# Sheet2.net
KiCad netlist of a schematic drawn in Altium Designer
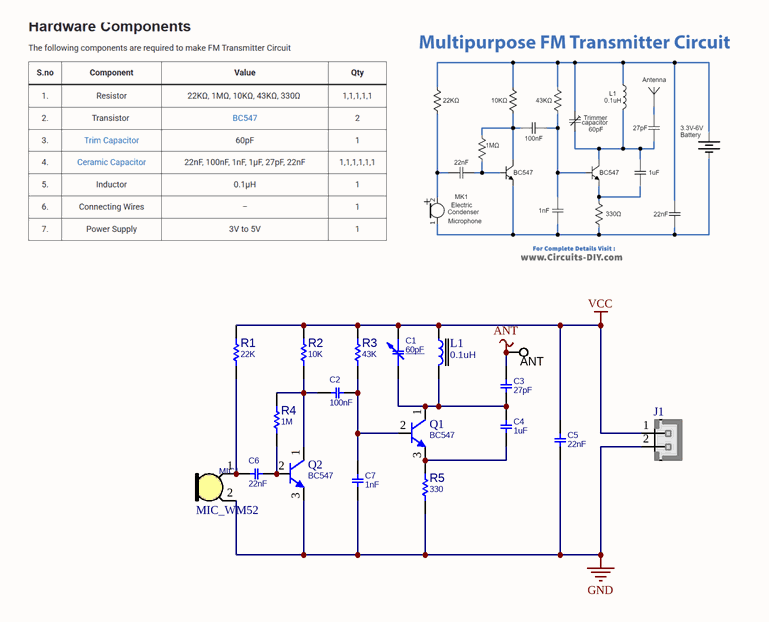
[diagram p0: Sheet2.SchDoc]

(export (version "E")
  (design (tool "Eeschema 10.0.6"))
  (components
    (comp (ref "ANT")
      (value "TESTPOINT_PROBE")
      (footprint "TPTHD_A")
      (description "TEST POINT")
      (fields (field (name "MANF") "MANF") (field (name "MANF_P#") "MANF_P#"))
      (libsource (lib "test-tp_jumper") (part "TESTPOINT_PROBE"))
    )
    (comp (ref "C1")
      (value "60pF")
      (footprint "CTRM_6X6")
      (description "CAP, THD, TRIMMER")
      (fields (field (name "MANF_P#") "MANF_PART#") (field (name "MANF") "MANF"))
      (libsource (lib "passive_thd") (part "CAP_THD_TRIMMER"))
    )
    (comp (ref "C2")
      (value "100nF")
      (footprint "C_CER_D5")
      (description "CAP, THD, CER MULTI LAYER,")
      (fields (field (name "MANF_P#") "MANF_PART#") (field (name "MANF") "MANF"))
      (libsource (lib "passive_thd") (part "CAP_THD_CER"))
    )
    (comp (ref "C3")
      (value "27pF")
      (footprint "C_CER_D5")
      (description "CAP, THD, CER MULTI LAYER,")
      (fields (field (name "MANF_P#") "MANF_PART#") (field (name "MANF") "MANF"))
      (libsource (lib "passive_thd") (part "CAP_THD_CER"))
    )
    (comp (ref "C4")
      (value "1uF")
      (footprint "C_CER_D5")
      (description "CAP, THD, CER MULTI LAYER,")
      (fields (field (name "MANF_P#") "MANF_PART#") (field (name "MANF") "MANF"))
      (libsource (lib "passive_thd") (part "CAP_THD_CER"))
    )
    (comp (ref "C5")
      (value "22nF")
      (footprint "C_CER_D5")
      (description "CAP, THD, CER MULTI LAYER,")
      (fields (field (name "MANF_P#") "MANF_PART#") (field (name "MANF") "MANF"))
      (libsource (lib "passive_thd") (part "CAP_THD_CER"))
    )
    (comp (ref "C6")
      (value "22nF")
      (footprint "C_CER_D5")
      (description "CAP, THD, CER MULTI LAYER,")
      (fields (field (name "MANF_P#") "MANF_PART#") (field (name "MANF") "MANF"))
      (libsource (lib "passive_thd") (part "CAP_THD_CER"))
    )
    (comp (ref "C7")
      (value "1nF")
      (footprint "C_CER_D5")
      (description "CAP, THD, CER MULTI LAYER,")
      (fields (field (name "MANF_P#") "MANF_PART#") (field (name "MANF") "MANF"))
      (libsource (lib "passive_thd") (part "CAP_THD_CER"))
    )
    (comp (ref "J1")
      (value "HHDR_2")
      (footprint "XH_2")
      (description "JST-XH pitch: 2.5mm")
      (libsource (lib "conn_wire2board") (part "XH_2"))
    )
    (comp (ref "L1")
      (value "0.1uH")
      (footprint "LT_AX025")
      (description "INDUCTOR, THD")
      (libsource (lib "passive_thd") (part "IND_THD"))
    )
    (comp (ref "MIC1")
      (value "MIC_WM52")
      (footprint "MIC_C6")
      (description "MICROPHONE OMNI")
      (fields (field (name "MANF_P#") "WM52BM"))
      (libsource (lib "audio_mic_spk") (part "MIC_WM-52"))
    )
    (comp (ref "Q1")
      (value "BC547")
      (footprint "TO92_3")
      (description "BJT, NPN, 45v, 0.1A, THD, TO92")
      (fields (field (name "MANF") "FAIRCHILD"))
      (libsource (lib "transistor_bjt") (part "NPN_BC547_TO92"))
    )
    (comp (ref "Q2")
      (value "BC547")
      (footprint "TO92_3")
      (description "BJT, NPN, 45v, 0.1A, THD, TO92")
      (fields (field (name "MANF") "FAIRCHILD"))
      (libsource (lib "transistor_bjt") (part "NPN_BC547_TO92"))
    )
    (comp (ref "R1")
      (value "22K")
      (footprint "R025W_AX04")
      (description "RESISTOR, THD")
      (fields (field (name "MANF_P#") "RK73H1ETTP4701F") (field (name "MANF") "KOA SPEER"))
      (libsource (lib "passive") (part "RES_THD"))
    )
    (comp (ref "R2")
      (value "10K")
      (footprint "R025W_AX04")
      (description "RESISTOR, THD")
      (fields (field (name "MANF_P#") "RK73H1ETTP4701F") (field (name "MANF") "KOA SPEER"))
      (libsource (lib "passive") (part "RES_THD"))
    )
    (comp (ref "R3")
      (value "43K")
      (footprint "R025W_AX04")
      (description "RESISTOR, THD")
      (fields (field (name "MANF_P#") "RK73H1ETTP4701F") (field (name "MANF") "KOA SPEER"))
      (libsource (lib "passive") (part "RES_THD"))
    )
    (comp (ref "R4")
      (value "1M")
      (footprint "R025W_AX04")
      (description "RESISTOR, THD")
      (fields (field (name "MANF_P#") "RK73H1ETTP4701F") (field (name "MANF") "KOA SPEER"))
      (libsource (lib "passive") (part "RES_THD"))
    )
    (comp (ref "R5")
      (value "330")
      (footprint "R025W_AX04")
      (description "RESISTOR, THD")
      (fields (field (name "MANF_P#") "RK73H1ETTP4701F") (field (name "MANF") "KOA SPEER"))
      (libsource (lib "passive") (part "RES_THD"))
    )
  )
  (nets
    (net (code "1") (name "ANT") (class "Default")
      (node (ref "ANT") (pin "1") (pinfunction "1_1") (pintype "passive"))
      (node (ref "C3") (pin "2") (pinfunction "2_2") (pintype "passive"))
    )
    (net (code "2") (name "GND") (class "Default")
      (node (ref "C5") (pin "1") (pinfunction "1_1") (pintype "passive"))
      (node (ref "C7") (pin "1") (pinfunction "1_1") (pintype "passive"))
      (node (ref "J1") (pin "2") (pinfunction "2_2") (pintype "passive"))
      (node (ref "MIC1") (pin "2") (pinfunction "GND_2") (pintype "passive"))
      (node (ref "Q2") (pin "3") (pinfunction "E_3") (pintype "passive"))
      (node (ref "R5") (pin "1") (pinfunction "1_1") (pintype "passive"))
    )
    (net (code "3") (name "Net-(MIC1-OUT)") (class "Default")
      (node (ref "C6") (pin "2") (pinfunction "2_2") (pintype "passive"))
      (node (ref "MIC1") (pin "1") (pinfunction "OUT_1") (pintype "passive"))
      (node (ref "R1") (pin "1") (pinfunction "1_1") (pintype "passive"))
    )
    (net (code "4") (name "Net-(Q1-B)") (class "Default")
      (node (ref "C2") (pin "1") (pinfunction "1_1") (pintype "passive"))
      (node (ref "C7") (pin "2") (pinfunction "2_2") (pintype "passive"))
      (node (ref "Q1") (pin "2") (pinfunction "B_2") (pintype "passive"))
      (node (ref "R3") (pin "1") (pinfunction "1_1") (pintype "passive"))
    )
    (net (code "5") (name "Net-(Q1-C)") (class "Default")
      (node (ref "C1") (pin "1") (pinfunction "1_1") (pintype "passive"))
      (node (ref "C3") (pin "1") (pinfunction "1_1") (pintype "passive"))
      (node (ref "C4") (pin "2") (pinfunction "2_2") (pintype "passive"))
      (node (ref "L1") (pin "2") (pinfunction "2_2") (pintype "passive"))
      (node (ref "Q1") (pin "1") (pinfunction "C_1") (pintype "passive"))
    )
    (net (code "6") (name "Net-(Q1-E)") (class "Default")
      (node (ref "C4") (pin "1") (pinfunction "1_1") (pintype "passive"))
      (node (ref "Q1") (pin "3") (pinfunction "E_3") (pintype "passive"))
      (node (ref "R5") (pin "2") (pinfunction "2_2") (pintype "passive"))
    )
    (net (code "7") (name "Net-(Q2-B)") (class "Default")
      (node (ref "C6") (pin "1") (pinfunction "1_1") (pintype "passive"))
      (node (ref "Q2") (pin "2") (pinfunction "B_2") (pintype "passive"))
      (node (ref "R4") (pin "1") (pinfunction "1_1") (pintype "passive"))
    )
    (net (code "8") (name "Net-(Q2-C)") (class "Default")
      (node (ref "C2") (pin "2") (pinfunction "2_2") (pintype "passive"))
      (node (ref "Q2") (pin "1") (pinfunction "C_1") (pintype "passive"))
      (node (ref "R2") (pin "1") (pinfunction "1_1") (pintype "passive"))
      (node (ref "R4") (pin "2") (pinfunction "2_2") (pintype "passive"))
    )
    (net (code "9") (name "VCC") (class "Default")
      (node (ref "C1") (pin "2") (pinfunction "2_2") (pintype "passive"))
      (node (ref "C5") (pin "2") (pinfunction "2_2") (pintype "passive"))
      (node (ref "J1") (pin "1") (pinfunction "1_1") (pintype "passive"))
      (node (ref "L1") (pin "1") (pinfunction "1_1") (pintype "passive"))
      (node (ref "R1") (pin "2") (pinfunction "2_2") (pintype "passive"))
      (node (ref "R2") (pin "2") (pinfunction "2_2") (pintype "passive"))
      (node (ref "R3") (pin "2") (pinfunction "2_2") (pintype "passive"))
    )
  )
)
